# Sparkfun_TMP117_ESP12-E.net
KiCad netlist of a schematic drawn in EAGLE
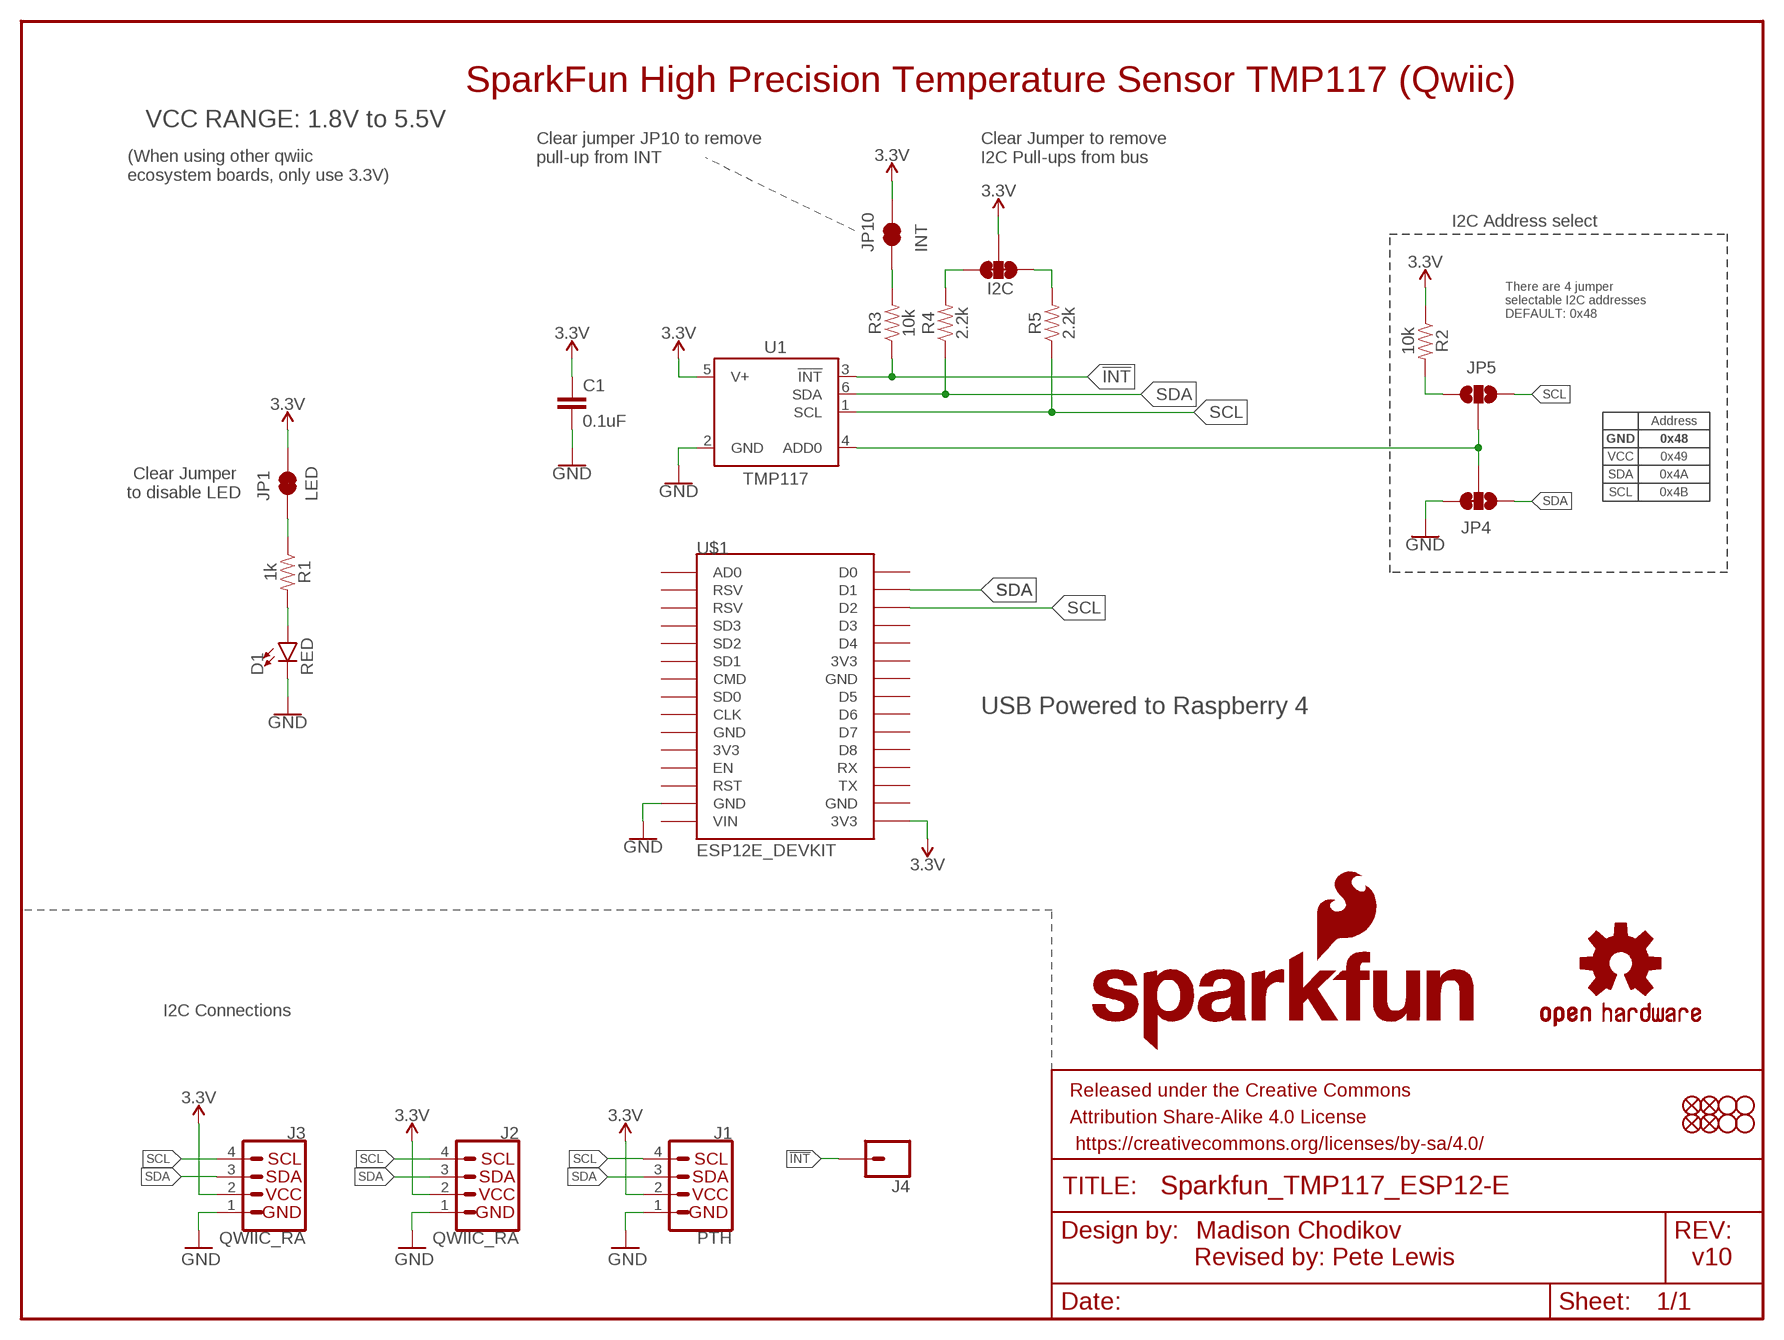
[diagram p0: schematic, sheet 1]

(export (version "E")
  (design (tool "Eeschema 10.0.6"))
  (components
    (comp (ref "C1")
      (value "0.1uF")
      (footprint "eagle-import:0603")
      (libsource (lib "eagle-import") (part "0.1UF-0603-25V-(+80/-20%)"))
    )
    (comp (ref "D1")
      (value "RED")
      (footprint "eagle-import:LED-0603")
      (libsource (lib "eagle-import") (part "LED-RED0603"))
    )
    (comp (ref "FD1")
      (value "FIDUCIALUFIDUCIAL")
      (footprint "eagle-import:FIDUCIAL-MICRO")
      (libsource (lib "eagle-import") (part "FIDUCIALUFIDUCIAL"))
    )
    (comp (ref "FD2")
      (value "FIDUCIALUFIDUCIAL")
      (footprint "eagle-import:FIDUCIAL-MICRO")
      (libsource (lib "eagle-import") (part "FIDUCIALUFIDUCIAL"))
    )
    (comp (ref "FD3")
      (value "FIDUCIALUFIDUCIAL")
      (footprint "eagle-import:FIDUCIAL-MICRO")
      (libsource (lib "eagle-import") (part "FIDUCIALUFIDUCIAL"))
    )
    (comp (ref "FD4")
      (value "FIDUCIALUFIDUCIAL")
      (footprint "eagle-import:FIDUCIAL-MICRO")
      (libsource (lib "eagle-import") (part "FIDUCIALUFIDUCIAL"))
    )
    (comp (ref "FRAME1")
      (value "FRAME-LETTER")
      (footprint "eagle-import:CREATIVE_COMMONS")
      (libsource (lib "eagle-import") (part "FRAME-LETTER"))
    )
    (comp (ref "I2C")
      (value "JUMPER-SMT_3_2-NC_TRACE_SILK")
      (footprint "eagle-import:SMT-JUMPER_3_2-NC_TRACE_SILK")
      (libsource (lib "eagle-import") (part "JUMPER-SMT_3_2-NC_TRACE_SILK"))
    )
    (comp (ref "J1")
      (value "PTH")
      (footprint "eagle-import:1X04_NO_SILK")
      (libsource (lib "eagle-import") (part "I2C_STANDARD_NO_SILK"))
    )
    (comp (ref "J2")
      (value "QWIIC_RA")
      (footprint "eagle-import:JST04_1MM_RA")
      (libsource (lib "eagle-import") (part "QWIIC_CONNECTORJS-1MM"))
    )
    (comp (ref "J3")
      (value "QWIIC_RA")
      (footprint "eagle-import:JST04_1MM_RA")
      (libsource (lib "eagle-import") (part "QWIIC_CONNECTORJS-1MM"))
    )
    (comp (ref "J4")
      (value "CONN_01PTH_NO_SILK_YES_STOP")
      (footprint "eagle-import:1X01_NO_SILK")
      (libsource (lib "eagle-import") (part "CONN_01PTH_NO_SILK_YES_STOP"))
    )
    (comp (ref "JP1")
      (value "LED")
      (footprint "eagle-import:SMT-JUMPER_2_NC_TRACE_SILK")
      (libsource (lib "eagle-import") (part "JUMPER-SMT_2_NC_TRACE_SILK"))
    )
    (comp (ref "JP2")
      (value "STAND-OFF")
      (footprint "eagle-import:STAND-OFF")
      (libsource (lib "eagle-import") (part "STAND-OFF"))
    )
    (comp (ref "JP3")
      (value "STAND-OFF")
      (footprint "eagle-import:STAND-OFF")
      (libsource (lib "eagle-import") (part "STAND-OFF"))
    )
    (comp (ref "JP4")
      (value "JUMPER-SMT_3_1-NC_TRACE_NO-SILK")
      (footprint "eagle-import:SMT-JUMPER_3_1-NC_TRACE_NO-SILK")
      (libsource (lib "eagle-import") (part "JUMPER-SMT_3_1-NC_TRACE_NO-SILK"))
    )
    (comp (ref "JP5")
      (value "JUMPER-SMT_3_NO_NO_SILK")
      (footprint "eagle-import:SMT-JUMPER_3_0-NO_TRACE_NO-SILK")
      (libsource (lib "eagle-import") (part "JUMPER-SMT_3_NO_NO_SILK"))
    )
    (comp (ref "JP8")
      (value "STAND-OFF")
      (footprint "eagle-import:STAND-OFF")
      (libsource (lib "eagle-import") (part "STAND-OFF"))
    )
    (comp (ref "JP9")
      (value "STAND-OFF")
      (footprint "eagle-import:STAND-OFF")
      (libsource (lib "eagle-import") (part "STAND-OFF"))
    )
    (comp (ref "JP10")
      (value "INT")
      (footprint "eagle-import:SMT-JUMPER_2_NC_TRACE_SILK")
      (libsource (lib "eagle-import") (part "JUMPER-SMT_2_NC_TRACE_SILK"))
    )
    (comp (ref "LOGO1")
      (value "OSHW-LOGOMINI")
      (footprint "eagle-import:OSHW-LOGO-MINI")
      (libsource (lib "eagle-import") (part "OSHW-LOGOMINI"))
    )
    (comp (ref "LOGO4")
      (value "SFE_LOGO_NAME_FLAME.1_INCH")
      (footprint "eagle-import:SFE_LOGO_NAME_FLAME_.1")
      (libsource (lib "eagle-import") (part "SFE_LOGO_NAME_FLAME.1_INCH"))
    )
    (comp (ref "R1")
      (value "1k")
      (footprint "eagle-import:0603")
      (libsource (lib "eagle-import") (part "1KOHM-0603-1/10W-1%"))
    )
    (comp (ref "R2")
      (value "10k")
      (footprint "eagle-import:0603")
      (libsource (lib "eagle-import") (part "10KOHM-0603-1/10W-1%"))
    )
    (comp (ref "R3")
      (value "10k")
      (footprint "eagle-import:0603")
      (libsource (lib "eagle-import") (part "10KOHM-0603-1/10W-1%"))
    )
    (comp (ref "R4")
      (value "2.2k")
      (footprint "eagle-import:0603")
      (libsource (lib "eagle-import") (part "2.2KOHM-0603-1/10W-1%"))
    )
    (comp (ref "R5")
      (value "2.2k")
      (footprint "eagle-import:0603")
      (libsource (lib "eagle-import") (part "2.2KOHM-0603-1/10W-1%"))
    )
    (comp (ref "U$1")
      (value "ESP12E_DEVKIT")
      (footprint "eagle-import:ESP12E_DEVKIT")
      (libsource (lib "eagle-import") (part "ESP12E_DEVKIT"))
    )
    (comp (ref "U1")
      (value "TMP117")
      (footprint "eagle-import:TMP117")
      (libsource (lib "eagle-import") (part "TMP117"))
    )
  )
  (nets
    (net (code "1") (name "/~{INT}") (class "Default")
      (node (ref "J4") (pin "1") (pinfunction "1_1") (pintype "passive"))
      (node (ref "R3") (pin "1") (pinfunction "1_1") (pintype "passive"))
      (node (ref "U1") (pin "3") (pinfunction "~{INT}_3") (pintype "bidirectional"))
    )
    (net (code "2") (name "3.3V") (class "Default")
      (node (ref "C1") (pin "1") (pinfunction "1_1") (pintype "passive"))
      (node (ref "I2C") (pin "2") (pinfunction "2_2") (pintype "passive"))
      (node (ref "J1") (pin "2") (pinfunction "2_2") (pintype "power_in"))
      (node (ref "J2") (pin "2") (pinfunction "2_2") (pintype "power_in"))
      (node (ref "J3") (pin "2") (pinfunction "2_2") (pintype "power_in"))
      (node (ref "JP1") (pin "2") (pinfunction "2_2") (pintype "passive"))
      (node (ref "JP10") (pin "2") (pinfunction "2_2") (pintype "passive"))
      (node (ref "R2") (pin "1") (pinfunction "1_1") (pintype "passive"))
      (node (ref "U$1") (pin "3V3@2") (pinfunction "3V3_3V3@2") (pintype "bidirectional"))
      (node (ref "U1") (pin "5") (pinfunction "V+_5") (pintype "power_in"))
    )
    (net (code "3") (name "GND") (class "Default")
      (node (ref "C1") (pin "2") (pinfunction "2_2") (pintype "passive"))
      (node (ref "D1") (pin "C") (pinfunction "C_C") (pintype "passive"))
      (node (ref "J1") (pin "1") (pinfunction "1_1") (pintype "power_in"))
      (node (ref "J2") (pin "1") (pinfunction "1_1") (pintype "power_in"))
      (node (ref "J3") (pin "1") (pinfunction "1_1") (pintype "power_in"))
      (node (ref "JP4") (pin "3") (pinfunction "3_3") (pintype "passive"))
      (node (ref "U$1") (pin "GND@1") (pinfunction "GND_GND@1") (pintype "bidirectional"))
      (node (ref "U1") (pin "2") (pinfunction "GND_2") (pintype "bidirectional"))
    )
    (net (code "4") (name "Net-(D1-PadA)") (class "Default")
      (node (ref "D1") (pin "A") (pinfunction "A_A") (pintype "passive"))
      (node (ref "R1") (pin "2") (pinfunction "2_2") (pintype "passive"))
    )
    (net (code "5") (name "Net-(I2C-Pad1)") (class "Default")
      (node (ref "I2C") (pin "1") (pinfunction "1_1") (pintype "passive"))
      (node (ref "R5") (pin "2") (pinfunction "2_2") (pintype "passive"))
    )
    (net (code "6") (name "Net-(I2C-Pad3)") (class "Default")
      (node (ref "I2C") (pin "3") (pinfunction "3_3") (pintype "passive"))
      (node (ref "R4") (pin "2") (pinfunction "2_2") (pintype "passive"))
    )
    (net (code "7") (name "Net-(JP1-Pad1)") (class "Default")
      (node (ref "JP1") (pin "1") (pinfunction "1_1") (pintype "passive"))
      (node (ref "R1") (pin "1") (pinfunction "1_1") (pintype "passive"))
    )
    (net (code "8") (name "Net-(JP5-Pad1)") (class "Default")
      (node (ref "JP5") (pin "1") (pinfunction "1_1") (pintype "passive"))
      (node (ref "R2") (pin "2") (pinfunction "2_2") (pintype "passive"))
    )
    (net (code "9") (name "Net-(JP10-Pad1)") (class "Default")
      (node (ref "JP10") (pin "1") (pinfunction "1_1") (pintype "passive"))
      (node (ref "R3") (pin "2") (pinfunction "2_2") (pintype "passive"))
    )
    (net (code "10") (name "Net-(U1-ADD0)") (class "Default")
      (node (ref "JP4") (pin "2") (pinfunction "2_2") (pintype "passive"))
      (node (ref "JP5") (pin "2") (pinfunction "2_2") (pintype "passive"))
      (node (ref "U1") (pin "4") (pinfunction "ADD0_4") (pintype "bidirectional"))
    )
    (net (code "11") (name "SCL") (class "Default")
      (node (ref "J1") (pin "4") (pinfunction "4_4") (pintype "passive"))
      (node (ref "J2") (pin "4") (pinfunction "4_4") (pintype "passive"))
      (node (ref "J3") (pin "4") (pinfunction "4_4") (pintype "passive"))
      (node (ref "JP5") (pin "3") (pinfunction "3_3") (pintype "passive"))
      (node (ref "R5") (pin "1") (pinfunction "1_1") (pintype "passive"))
      (node (ref "U$1") (pin "D2") (pinfunction "D2_D2") (pintype "bidirectional"))
      (node (ref "U1") (pin "1") (pinfunction "SCL_1") (pintype "bidirectional"))
    )
    (net (code "12") (name "SDA") (class "Default")
      (node (ref "J1") (pin "3") (pinfunction "3_3") (pintype "passive"))
      (node (ref "J2") (pin "3") (pinfunction "3_3") (pintype "passive"))
      (node (ref "J3") (pin "3") (pinfunction "3_3") (pintype "passive"))
      (node (ref "JP4") (pin "1") (pinfunction "1_1") (pintype "passive"))
      (node (ref "R4") (pin "1") (pinfunction "1_1") (pintype "passive"))
      (node (ref "U$1") (pin "D1") (pinfunction "D1_D1") (pintype "bidirectional"))
      (node (ref "U1") (pin "6") (pinfunction "SDA_6") (pintype "bidirectional"))
    )
    (net (code "13") (name "unconnected-(U$1-3V3-Pad3V3@0)") (class "Default")
      (node (ref "U$1") (pin "3V3@0") (pinfunction "3V3_3V3@0") (pintype "bidirectional"))
    )
    (net (code "14") (name "unconnected-(U$1-3V3-Pad3V3@1)") (class "Default")
      (node (ref "U$1") (pin "3V3@1") (pinfunction "3V3_3V3@1") (pintype "bidirectional"))
    )
    (net (code "15") (name "unconnected-(U$1-GND-PadGND@0)") (class "Default")
      (node (ref "U$1") (pin "GND@0") (pinfunction "GND_GND@0") (pintype "bidirectional"))
    )
    (net (code "16") (name "unconnected-(U$1-GND-PadGND@2)") (class "Default")
      (node (ref "U$1") (pin "GND@2") (pinfunction "GND_GND@2") (pintype "bidirectional"))
    )
    (net (code "17") (name "unconnected-(U$1-GND-PadGND@3)") (class "Default")
      (node (ref "U$1") (pin "GND@3") (pinfunction "GND_GND@3") (pintype "bidirectional"))
    )
    (net (code "18") (name "unconnected-(U$1-PadAD0)") (class "Default")
      (node (ref "U$1") (pin "AD0") (pinfunction "AD0_AD0") (pintype "bidirectional"))
    )
    (net (code "19") (name "unconnected-(U$1-PadCLK)") (class "Default")
      (node (ref "U$1") (pin "CLK") (pinfunction "CLK_CLK") (pintype "bidirectional"))
    )
    (net (code "20") (name "unconnected-(U$1-PadCMD)") (class "Default")
      (node (ref "U$1") (pin "CMD") (pinfunction "CMD_CMD") (pintype "bidirectional"))
    )
    (net (code "21") (name "unconnected-(U$1-PadD0)") (class "Default")
      (node (ref "U$1") (pin "D0") (pinfunction "D0_D0") (pintype "bidirectional"))
    )
    (net (code "22") (name "unconnected-(U$1-PadD3)") (class "Default")
      (node (ref "U$1") (pin "D3") (pinfunction "D3_D3") (pintype "bidirectional"))
    )
    (net (code "23") (name "unconnected-(U$1-PadD4)") (class "Default")
      (node (ref "U$1") (pin "D4") (pinfunction "D4_D4") (pintype "bidirectional"))
    )
    (net (code "24") (name "unconnected-(U$1-PadD5)") (class "Default")
      (node (ref "U$1") (pin "D5") (pinfunction "D5_D5") (pintype "bidirectional"))
    )
    (net (code "25") (name "unconnected-(U$1-PadD6)") (class "Default")
      (node (ref "U$1") (pin "D6") (pinfunction "D6_D6") (pintype "bidirectional"))
    )
    (net (code "26") (name "unconnected-(U$1-PadD7)") (class "Default")
      (node (ref "U$1") (pin "D7") (pinfunction "D7_D7") (pintype "bidirectional"))
    )
    (net (code "27") (name "unconnected-(U$1-PadD8)") (class "Default")
      (node (ref "U$1") (pin "D8") (pinfunction "D8_D8") (pintype "bidirectional"))
    )
    (net (code "28") (name "unconnected-(U$1-PadEN)") (class "Default")
      (node (ref "U$1") (pin "EN") (pinfunction "EN_EN") (pintype "bidirectional"))
    )
    (net (code "29") (name "unconnected-(U$1-PadRST)") (class "Default")
      (node (ref "U$1") (pin "RST") (pinfunction "RST_RST") (pintype "bidirectional"))
    )
    (net (code "30") (name "unconnected-(U$1-PadRX)") (class "Default")
      (node (ref "U$1") (pin "RX") (pinfunction "RX_RX") (pintype "bidirectional"))
    )
    (net (code "31") (name "unconnected-(U$1-PadSD0)") (class "Default")
      (node (ref "U$1") (pin "SD0") (pinfunction "SD0_SD0") (pintype "bidirectional"))
    )
    (net (code "32") (name "unconnected-(U$1-PadSD1)") (class "Default")
      (node (ref "U$1") (pin "SD1") (pinfunction "SD1_SD1") (pintype "bidirectional"))
    )
    (net (code "33") (name "unconnected-(U$1-PadSD2)") (class "Default")
      (node (ref "U$1") (pin "SD2") (pinfunction "SD2_SD2") (pintype "bidirectional"))
    )
    (net (code "34") (name "unconnected-(U$1-PadSD3)") (class "Default")
      (node (ref "U$1") (pin "SD3") (pinfunction "SD3_SD3") (pintype "bidirectional"))
    )
    (net (code "35") (name "unconnected-(U$1-PadTX)") (class "Default")
      (node (ref "U$1") (pin "TX") (pinfunction "TX_TX") (pintype "bidirectional"))
    )
    (net (code "36") (name "unconnected-(U$1-PadVIN)") (class "Default")
      (node (ref "U$1") (pin "VIN") (pinfunction "VIN_VIN") (pintype "bidirectional"))
    )
    (net (code "37") (name "unconnected-(U$1-RSV-PadRSV@0)") (class "Default")
      (node (ref "U$1") (pin "RSV@0") (pinfunction "RSV_RSV@0") (pintype "bidirectional"))
    )
    (net (code "38") (name "unconnected-(U$1-RSV-PadRSV@1)") (class "Default")
      (node (ref "U$1") (pin "RSV@1") (pinfunction "RSV_RSV@1") (pintype "bidirectional"))
    )
  )
)
